# obc_flash.net
KiCad netlist of a schematic drawn in Altium Designer
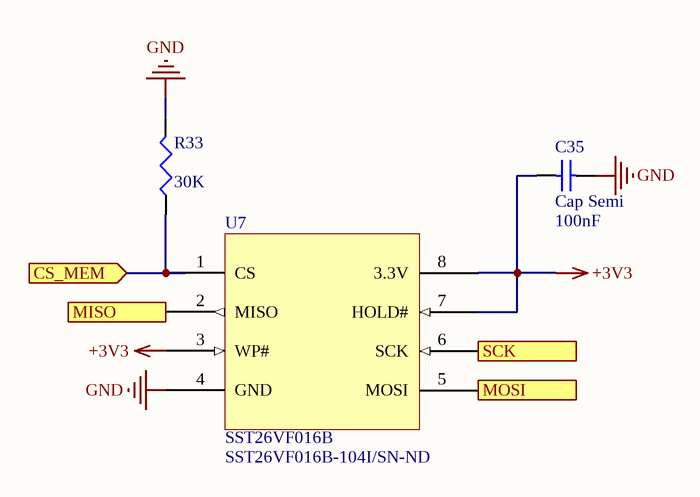
[diagram p0: obc_flash (1).SchDoc]

(export (version "E")
  (design (tool "Eeschema 10.0.6"))
  (components
    (comp (ref "C35")
      (value "Cap Semi")
      (footprint "1608[0603]")
      (description "Capacitor (Semiconductor SIM Model)")
      (fields (field (name "ALTIUM_VALUE") "100nF") (field (name "PUBLISHER") "Altium Limited"))
      (libsource (lib "Miscellaneous Devices") (part "Cap Semi"))
    )
    (comp (ref "R33")
      (value "30K")
      (footprint "J1-0603")
      (description "30K Pull-up resistor for RST. See page")
      (fields (field (name "PUBLISHER") "Altium Limited"))
      (libsource (lib "Miscellaneous Devices") (part "Res3"))
    )
    (comp (ref "U7")
      (value "SST26VF016B")
      (footprint "SOIC127P500X600-8N")
      (description "2.5V/3.0V 16 Mbit Serial Quad I/O (SQI) Flash Memory")
      (fields (field (name "SUPPLIER PART NUMBER 1") "SST26VF016B-104I/SN-ND"))
      (libsource (lib "heron-general") (part "SST26VF016B"))
    )
  )
  (nets
    (net (code "1") (name "+3V3") (class "Default")
      (node (ref "C35") (pin "1") (pinfunction "1_1") (pintype "passive"))
      (node (ref "U7") (pin "3") (pinfunction "WP#_3") (pintype "input"))
      (node (ref "U7") (pin "7") (pinfunction "HOLD#_7") (pintype "input"))
      (node (ref "U7") (pin "8") (pinfunction "3.3V_8") (pintype "power_in"))
    )
    (net (code "2") (name "/CS_MEM") (class "Default")
      (node (ref "R33") (pin "1") (pinfunction "1_1") (pintype "passive"))
      (node (ref "U7") (pin "1") (pinfunction "CS_1") (pintype "passive"))
    )
    (net (code "3") (name "/MISO") (class "Default")
      (node (ref "U7") (pin "2") (pinfunction "MISO_2") (pintype "output"))
    )
    (net (code "4") (name "/MOSI") (class "Default")
      (node (ref "U7") (pin "5") (pinfunction "MOSI_5") (pintype "passive"))
    )
    (net (code "5") (name "/SCK") (class "Default")
      (node (ref "U7") (pin "6") (pinfunction "SCK_6") (pintype "input"))
    )
    (net (code "6") (name "GND") (class "Default")
      (node (ref "C35") (pin "2") (pinfunction "2_2") (pintype "passive"))
      (node (ref "R33") (pin "2") (pinfunction "2_2") (pintype "passive"))
      (node (ref "U7") (pin "4") (pinfunction "GND_4") (pintype "power_in"))
    )
  )
)
